# cherrymx1.net
KiCad netlist of a schematic drawn in EAGLE
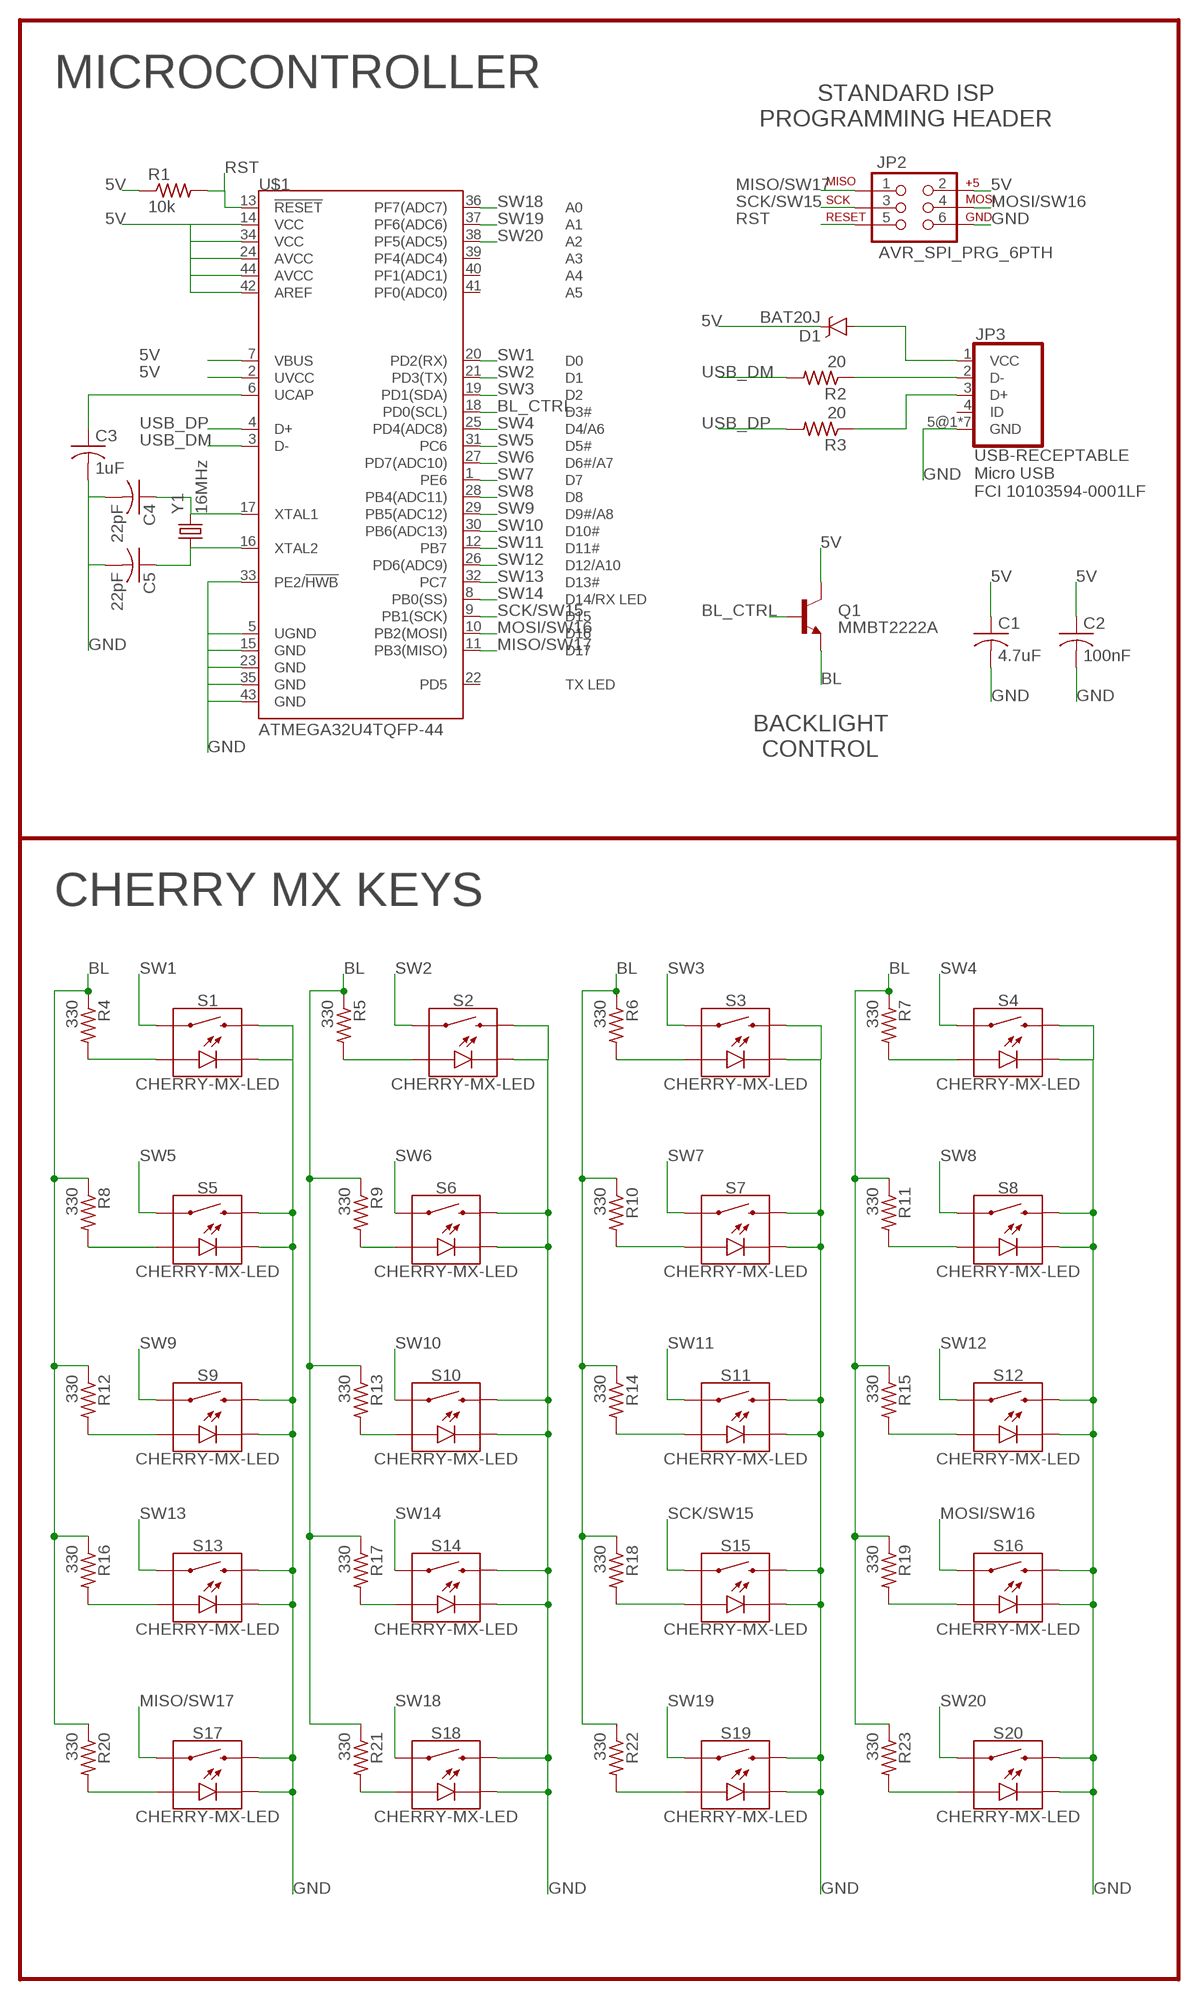
[diagram p0: schematic, sheet 1]

(export (version "E")
  (design (tool "Eeschema 10.0.6"))
  (components
    (comp (ref "C1")
      (value "4.7uF")
      (footprint "eagle-import:C0603")
      (libsource (lib "eagle-import") (part "C-USC0603"))
    )
    (comp (ref "C2")
      (value "100nF")
      (footprint "eagle-import:C0603")
      (libsource (lib "eagle-import") (part "C-USC0603"))
    )
    (comp (ref "C3")
      (value "1uF")
      (footprint "eagle-import:C0603")
      (libsource (lib "eagle-import") (part "C-USC0603"))
    )
    (comp (ref "C4")
      (value "22pF")
      (footprint "eagle-import:C0603")
      (libsource (lib "eagle-import") (part "C-USC0603"))
    )
    (comp (ref "C5")
      (value "22pF")
      (footprint "eagle-import:C0603")
      (libsource (lib "eagle-import") (part "C-USC0603"))
    )
    (comp (ref "D1")
      (value "BAT20J")
      (footprint "eagle-import:SOD-323")
      (libsource (lib "eagle-import") (part "DIODE-SCHOTTKY-BAT20J"))
    )
    (comp (ref "JP2")
      (value "AVR_SPI_PRG_6PTH")
      (footprint "eagle-import:2X3")
      (libsource (lib "eagle-import") (part "AVR_SPI_PRG_6PTH"))
    )
    (comp (ref "JP3")
      (value "USB-RECEPTABLE")
      (footprint "eagle-import:FCI-10103594-0001LF")
      (libsource (lib "eagle-import") (part "USB-RECEPTABLE"))
    )
    (comp (ref "Q1")
      (value "MMBT2222A")
      (footprint "eagle-import:SOT23-3")
      (libsource (lib "eagle-import") (part "TRANSISTOR_NPNMMBT2222A"))
    )
    (comp (ref "R1")
      (value "10k")
      (footprint "eagle-import:R0603")
      (libsource (lib "eagle-import") (part "R-US_R0603"))
    )
    (comp (ref "R2")
      (value "20")
      (footprint "eagle-import:R0603")
      (libsource (lib "eagle-import") (part "R-US_R0603"))
    )
    (comp (ref "R3")
      (value "20")
      (footprint "eagle-import:R0603")
      (libsource (lib "eagle-import") (part "R-US_R0603"))
    )
    (comp (ref "R4")
      (value "330")
      (footprint "eagle-import:R0603")
      (libsource (lib "eagle-import") (part "R-US_R0603"))
    )
    (comp (ref "R5")
      (value "330")
      (footprint "eagle-import:R0603")
      (libsource (lib "eagle-import") (part "R-US_R0603"))
    )
    (comp (ref "R6")
      (value "330")
      (footprint "eagle-import:R0603")
      (libsource (lib "eagle-import") (part "R-US_R0603"))
    )
    (comp (ref "R7")
      (value "330")
      (footprint "eagle-import:R0603")
      (libsource (lib "eagle-import") (part "R-US_R0603"))
    )
    (comp (ref "R8")
      (value "330")
      (footprint "eagle-import:R0603")
      (libsource (lib "eagle-import") (part "R-US_R0603"))
    )
    (comp (ref "R9")
      (value "330")
      (footprint "eagle-import:R0603")
      (libsource (lib "eagle-import") (part "R-US_R0603"))
    )
    (comp (ref "R10")
      (value "330")
      (footprint "eagle-import:R0603")
      (libsource (lib "eagle-import") (part "R-US_R0603"))
    )
    (comp (ref "R11")
      (value "330")
      (footprint "eagle-import:R0603")
      (libsource (lib "eagle-import") (part "R-US_R0603"))
    )
    (comp (ref "R12")
      (value "330")
      (footprint "eagle-import:R0603")
      (libsource (lib "eagle-import") (part "R-US_R0603"))
    )
    (comp (ref "R13")
      (value "330")
      (footprint "eagle-import:R0603")
      (libsource (lib "eagle-import") (part "R-US_R0603"))
    )
    (comp (ref "R14")
      (value "330")
      (footprint "eagle-import:R0603")
      (libsource (lib "eagle-import") (part "R-US_R0603"))
    )
    (comp (ref "R15")
      (value "330")
      (footprint "eagle-import:R0603")
      (libsource (lib "eagle-import") (part "R-US_R0603"))
    )
    (comp (ref "R16")
      (value "330")
      (footprint "eagle-import:R0603")
      (libsource (lib "eagle-import") (part "R-US_R0603"))
    )
    (comp (ref "R17")
      (value "330")
      (footprint "eagle-import:R0603")
      (libsource (lib "eagle-import") (part "R-US_R0603"))
    )
    (comp (ref "R18")
      (value "330")
      (footprint "eagle-import:R0603")
      (libsource (lib "eagle-import") (part "R-US_R0603"))
    )
    (comp (ref "R19")
      (value "330")
      (footprint "eagle-import:R0603")
      (libsource (lib "eagle-import") (part "R-US_R0603"))
    )
    (comp (ref "R20")
      (value "330")
      (footprint "eagle-import:R0603")
      (libsource (lib "eagle-import") (part "R-US_R0603"))
    )
    (comp (ref "R21")
      (value "330")
      (footprint "eagle-import:R0603")
      (libsource (lib "eagle-import") (part "R-US_R0603"))
    )
    (comp (ref "R22")
      (value "330")
      (footprint "eagle-import:R0603")
      (libsource (lib "eagle-import") (part "R-US_R0603"))
    )
    (comp (ref "R23")
      (value "330")
      (footprint "eagle-import:R0603")
      (libsource (lib "eagle-import") (part "R-US_R0603"))
    )
    (comp (ref "S1")
      (value "CHERRY-MX-LED")
      (footprint "eagle-import:CHERRY-MX-LED")
      (libsource (lib "eagle-import") (part "CHERRY-MX-LED"))
    )
    (comp (ref "S2")
      (value "CHERRY-MX-LED")
      (footprint "eagle-import:CHERRY-MX-LED")
      (libsource (lib "eagle-import") (part "CHERRY-MX-LED"))
    )
    (comp (ref "S3")
      (value "CHERRY-MX-LED")
      (footprint "eagle-import:CHERRY-MX-LED")
      (libsource (lib "eagle-import") (part "CHERRY-MX-LED"))
    )
    (comp (ref "S4")
      (value "CHERRY-MX-LED")
      (footprint "eagle-import:CHERRY-MX-LED")
      (libsource (lib "eagle-import") (part "CHERRY-MX-LED"))
    )
    (comp (ref "S5")
      (value "CHERRY-MX-LED")
      (footprint "eagle-import:CHERRY-MX-LED")
      (libsource (lib "eagle-import") (part "CHERRY-MX-LED"))
    )
    (comp (ref "S6")
      (value "CHERRY-MX-LED")
      (footprint "eagle-import:CHERRY-MX-LED")
      (libsource (lib "eagle-import") (part "CHERRY-MX-LED"))
    )
    (comp (ref "S7")
      (value "CHERRY-MX-LED")
      (footprint "eagle-import:CHERRY-MX-LED")
      (libsource (lib "eagle-import") (part "CHERRY-MX-LED"))
    )
    (comp (ref "S8")
      (value "CHERRY-MX-LED")
      (footprint "eagle-import:CHERRY-MX-LED")
      (libsource (lib "eagle-import") (part "CHERRY-MX-LED"))
    )
    (comp (ref "S9")
      (value "CHERRY-MX-LED")
      (footprint "eagle-import:CHERRY-MX-LED")
      (libsource (lib "eagle-import") (part "CHERRY-MX-LED"))
    )
    (comp (ref "S10")
      (value "CHERRY-MX-LED")
      (footprint "eagle-import:CHERRY-MX-LED")
      (libsource (lib "eagle-import") (part "CHERRY-MX-LED"))
    )
    (comp (ref "S11")
      (value "CHERRY-MX-LED")
      (footprint "eagle-import:CHERRY-MX-LED")
      (libsource (lib "eagle-import") (part "CHERRY-MX-LED"))
    )
    (comp (ref "S12")
      (value "CHERRY-MX-LED")
      (footprint "eagle-import:CHERRY-MX-LED")
      (libsource (lib "eagle-import") (part "CHERRY-MX-LED"))
    )
    (comp (ref "S13")
      (value "CHERRY-MX-LED")
      (footprint "eagle-import:CHERRY-MX-LED")
      (libsource (lib "eagle-import") (part "CHERRY-MX-LED"))
    )
    (comp (ref "S14")
      (value "CHERRY-MX-LED")
      (footprint "eagle-import:CHERRY-MX-LED")
      (libsource (lib "eagle-import") (part "CHERRY-MX-LED"))
    )
    (comp (ref "S15")
      (value "CHERRY-MX-LED")
      (footprint "eagle-import:CHERRY-MX-LED")
      (libsource (lib "eagle-import") (part "CHERRY-MX-LED"))
    )
    (comp (ref "S16")
      (value "CHERRY-MX-LED")
      (footprint "eagle-import:CHERRY-MX-LED")
      (libsource (lib "eagle-import") (part "CHERRY-MX-LED"))
    )
    (comp (ref "S17")
      (value "CHERRY-MX-LED")
      (footprint "eagle-import:CHERRY-MX-LED")
      (libsource (lib "eagle-import") (part "CHERRY-MX-LED"))
    )
    (comp (ref "S18")
      (value "CHERRY-MX-LED")
      (footprint "eagle-import:CHERRY-MX-LED")
      (libsource (lib "eagle-import") (part "CHERRY-MX-LED"))
    )
    (comp (ref "S19")
      (value "CHERRY-MX-LED")
      (footprint "eagle-import:CHERRY-MX-LED")
      (libsource (lib "eagle-import") (part "CHERRY-MX-LED"))
    )
    (comp (ref "S20")
      (value "CHERRY-MX-LED")
      (footprint "eagle-import:CHERRY-MX-LED")
      (libsource (lib "eagle-import") (part "CHERRY-MX-LED"))
    )
    (comp (ref "U$1")
      (value "ATMEGA32U4TQFP-44")
      (footprint "eagle-import:TQFP44")
      (libsource (lib "eagle-import") (part "ATMEGA32U4TQFP-44"))
    )
    (comp (ref "Y1")
      (value "16MHz")
      (footprint "eagle-import:CRYSTAL-SMD-5X3")
      (libsource (lib "eagle-import") (part "CRYSTAL5X3"))
    )
  )
  (nets
    (net (code "1") (name "/5V") (class "Default")
      (node (ref "C1") (pin "1") (pinfunction "1_1") (pintype "passive"))
      (node (ref "C2") (pin "1") (pinfunction "1_1") (pintype "passive"))
      (node (ref "D1") (pin "C") (pinfunction "C_C") (pintype "passive"))
      (node (ref "JP2") (pin "2") (pinfunction "2_2") (pintype "passive"))
      (node (ref "Q1") (pin "3") (pinfunction "C_3") (pintype "passive"))
      (node (ref "R1") (pin "1") (pinfunction "1_1") (pintype "passive"))
      (node (ref "U$1") (pin "14") (pinfunction "VCC_14") (pintype "bidirectional"))
      (node (ref "U$1") (pin "2") (pinfunction "UVCC_2") (pintype "bidirectional"))
      (node (ref "U$1") (pin "24") (pinfunction "AVCC_24") (pintype "bidirectional"))
      (node (ref "U$1") (pin "34") (pinfunction "VCC_34") (pintype "bidirectional"))
      (node (ref "U$1") (pin "42") (pinfunction "AREF_42") (pintype "bidirectional"))
      (node (ref "U$1") (pin "44") (pinfunction "AVCC_44") (pintype "bidirectional"))
      (node (ref "U$1") (pin "7") (pinfunction "VBUS_7") (pintype "bidirectional"))
    )
    (net (code "2") (name "/BL") (class "Default")
      (node (ref "Q1") (pin "2") (pinfunction "E_2") (pintype "passive"))
      (node (ref "R10") (pin "1") (pinfunction "1_1") (pintype "passive"))
      (node (ref "R11") (pin "1") (pinfunction "1_1") (pintype "passive"))
      (node (ref "R12") (pin "1") (pinfunction "1_1") (pintype "passive"))
      (node (ref "R13") (pin "1") (pinfunction "1_1") (pintype "passive"))
      (node (ref "R14") (pin "1") (pinfunction "1_1") (pintype "passive"))
      (node (ref "R15") (pin "1") (pinfunction "1_1") (pintype "passive"))
      (node (ref "R16") (pin "1") (pinfunction "1_1") (pintype "passive"))
      (node (ref "R17") (pin "1") (pinfunction "1_1") (pintype "passive"))
      (node (ref "R18") (pin "1") (pinfunction "1_1") (pintype "passive"))
      (node (ref "R19") (pin "1") (pinfunction "1_1") (pintype "passive"))
      (node (ref "R20") (pin "1") (pinfunction "1_1") (pintype "passive"))
      (node (ref "R21") (pin "1") (pinfunction "1_1") (pintype "passive"))
      (node (ref "R22") (pin "1") (pinfunction "1_1") (pintype "passive"))
      (node (ref "R23") (pin "1") (pinfunction "1_1") (pintype "passive"))
      (node (ref "R4") (pin "1") (pinfunction "1_1") (pintype "passive"))
      (node (ref "R5") (pin "1") (pinfunction "1_1") (pintype "passive"))
      (node (ref "R6") (pin "1") (pinfunction "1_1") (pintype "passive"))
      (node (ref "R7") (pin "1") (pinfunction "1_1") (pintype "passive"))
      (node (ref "R8") (pin "1") (pinfunction "1_1") (pintype "passive"))
      (node (ref "R9") (pin "1") (pinfunction "1_1") (pintype "passive"))
    )
    (net (code "3") (name "/BL_CTRL") (class "Default")
      (node (ref "Q1") (pin "1") (pinfunction "B_1") (pintype "passive"))
      (node (ref "U$1") (pin "18") (pinfunction "PD0(SCL)_18") (pintype "bidirectional"))
    )
    (net (code "4") (name "/GND") (class "Default")
      (node (ref "C1") (pin "2") (pinfunction "2_2") (pintype "passive"))
      (node (ref "C2") (pin "2") (pinfunction "2_2") (pintype "passive"))
      (node (ref "C3") (pin "2") (pinfunction "2_2") (pintype "passive"))
      (node (ref "C4") (pin "2") (pinfunction "2_2") (pintype "passive"))
      (node (ref "C5") (pin "2") (pinfunction "2_2") (pintype "passive"))
      (node (ref "JP2") (pin "6") (pinfunction "6_6") (pintype "passive"))
      (node (ref "JP3") (pin "5@1") (pinfunction "GND_5@1") (pintype "bidirectional"))
      (node (ref "JP3") (pin "5@2") (pinfunction "GND_5@2") (pintype "bidirectional"))
      (node (ref "JP3") (pin "5@3") (pinfunction "GND_5@3") (pintype "bidirectional"))
      (node (ref "JP3") (pin "5@4") (pinfunction "GND_5@4") (pintype "bidirectional"))
      (node (ref "JP3") (pin "5@5") (pinfunction "GND_5@5") (pintype "bidirectional"))
      (node (ref "JP3") (pin "5@6") (pinfunction "GND_5@6") (pintype "bidirectional"))
      (node (ref "JP3") (pin "5@7") (pinfunction "GND_5@7") (pintype "bidirectional"))
      (node (ref "S1") (pin "K") (pinfunction "C_K") (pintype "passive"))
      (node (ref "S1") (pin "S2") (pinfunction "S2_S2") (pintype "passive"))
      (node (ref "S10") (pin "K") (pinfunction "C_K") (pintype "passive"))
      (node (ref "S10") (pin "S2") (pinfunction "S2_S2") (pintype "passive"))
      (node (ref "S11") (pin "K") (pinfunction "C_K") (pintype "passive"))
      (node (ref "S11") (pin "S2") (pinfunction "S2_S2") (pintype "passive"))
      (node (ref "S12") (pin "K") (pinfunction "C_K") (pintype "passive"))
      (node (ref "S12") (pin "S2") (pinfunction "S2_S2") (pintype "passive"))
      (node (ref "S13") (pin "K") (pinfunction "C_K") (pintype "passive"))
      (node (ref "S13") (pin "S2") (pinfunction "S2_S2") (pintype "passive"))
      (node (ref "S14") (pin "K") (pinfunction "C_K") (pintype "passive"))
      (node (ref "S14") (pin "S2") (pinfunction "S2_S2") (pintype "passive"))
      (node (ref "S15") (pin "K") (pinfunction "C_K") (pintype "passive"))
      (node (ref "S15") (pin "S2") (pinfunction "S2_S2") (pintype "passive"))
      (node (ref "S16") (pin "K") (pinfunction "C_K") (pintype "passive"))
      (node (ref "S16") (pin "S2") (pinfunction "S2_S2") (pintype "passive"))
      (node (ref "S17") (pin "K") (pinfunction "C_K") (pintype "passive"))
      (node (ref "S17") (pin "S2") (pinfunction "S2_S2") (pintype "passive"))
      (node (ref "S18") (pin "K") (pinfunction "C_K") (pintype "passive"))
      (node (ref "S18") (pin "S2") (pinfunction "S2_S2") (pintype "passive"))
      (node (ref "S19") (pin "K") (pinfunction "C_K") (pintype "passive"))
      (node (ref "S19") (pin "S2") (pinfunction "S2_S2") (pintype "passive"))
      (node (ref "S2") (pin "K") (pinfunction "C_K") (pintype "passive"))
      (node (ref "S2") (pin "S2") (pinfunction "S2_S2") (pintype "passive"))
      (node (ref "S20") (pin "K") (pinfunction "C_K") (pintype "passive"))
      (node (ref "S20") (pin "S2") (pinfunction "S2_S2") (pintype "passive"))
      (node (ref "S3") (pin "K") (pinfunction "C_K") (pintype "passive"))
      (node (ref "S3") (pin "S2") (pinfunction "S2_S2") (pintype "passive"))
      (node (ref "S4") (pin "K") (pinfunction "C_K") (pintype "passive"))
      (node (ref "S4") (pin "S2") (pinfunction "S2_S2") (pintype "passive"))
      (node (ref "S5") (pin "K") (pinfunction "C_K") (pintype "passive"))
      (node (ref "S5") (pin "S2") (pinfunction "S2_S2") (pintype "passive"))
      (node (ref "S6") (pin "K") (pinfunction "C_K") (pintype "passive"))
      (node (ref "S6") (pin "S2") (pinfunction "S2_S2") (pintype "passive"))
      (node (ref "S7") (pin "K") (pinfunction "C_K") (pintype "passive"))
      (node (ref "S7") (pin "S2") (pinfunction "S2_S2") (pintype "passive"))
      (node (ref "S8") (pin "K") (pinfunction "C_K") (pintype "passive"))
      (node (ref "S8") (pin "S2") (pinfunction "S2_S2") (pintype "passive"))
      (node (ref "S9") (pin "K") (pinfunction "C_K") (pintype "passive"))
      (node (ref "S9") (pin "S2") (pinfunction "S2_S2") (pintype "passive"))
      (node (ref "U$1") (pin "15") (pinfunction "GND_15") (pintype "bidirectional"))
      (node (ref "U$1") (pin "23") (pinfunction "GND_23") (pintype "bidirectional"))
      (node (ref "U$1") (pin "33") (pinfunction "PE2/~{HWB}_33") (pintype "bidirectional"))
      (node (ref "U$1") (pin "35") (pinfunction "GND_35") (pintype "bidirectional"))
      (node (ref "U$1") (pin "43") (pinfunction "GND_43") (pintype "bidirectional"))
      (node (ref "U$1") (pin "5") (pinfunction "UGND_5") (pintype "bidirectional"))
    )
    (net (code "5") (name "/MISO{slash}SW17") (class "Default")
      (node (ref "JP2") (pin "1") (pinfunction "1_1") (pintype "passive"))
      (node (ref "S17") (pin "S1") (pinfunction "S1_S1") (pintype "passive"))
      (node (ref "U$1") (pin "11") (pinfunction "PB3(MISO)_11") (pintype "bidirectional"))
    )
    (net (code "6") (name "/MOSI{slash}SW16") (class "Default")
      (node (ref "JP2") (pin "4") (pinfunction "4_4") (pintype "passive"))
      (node (ref "S16") (pin "S1") (pinfunction "S1_S1") (pintype "passive"))
      (node (ref "U$1") (pin "10") (pinfunction "PB2(MOSI)_10") (pintype "bidirectional"))
    )
    (net (code "7") (name "/RST") (class "Default")
      (node (ref "JP2") (pin "5") (pinfunction "5_5") (pintype "passive"))
      (node (ref "R1") (pin "2") (pinfunction "2_2") (pintype "passive"))
      (node (ref "U$1") (pin "13") (pinfunction "~{RESET}_13") (pintype "bidirectional"))
    )
    (net (code "8") (name "/SCK{slash}SW15") (class "Default")
      (node (ref "JP2") (pin "3") (pinfunction "3_3") (pintype "passive"))
      (node (ref "S15") (pin "S1") (pinfunction "S1_S1") (pintype "passive"))
      (node (ref "U$1") (pin "9") (pinfunction "PB1(SCK)_9") (pintype "bidirectional"))
    )
    (net (code "9") (name "/SW1") (class "Default")
      (node (ref "S1") (pin "S1") (pinfunction "S1_S1") (pintype "passive"))
      (node (ref "U$1") (pin "20") (pinfunction "PD2(RX)_20") (pintype "bidirectional"))
    )
    (net (code "10") (name "/SW2") (class "Default")
      (node (ref "S2") (pin "S1") (pinfunction "S1_S1") (pintype "passive"))
      (node (ref "U$1") (pin "21") (pinfunction "PD3(TX)_21") (pintype "bidirectional"))
    )
    (net (code "11") (name "/SW3") (class "Default")
      (node (ref "S3") (pin "S1") (pinfunction "S1_S1") (pintype "passive"))
      (node (ref "U$1") (pin "19") (pinfunction "PD1(SDA)_19") (pintype "bidirectional"))
    )
    (net (code "12") (name "/SW4") (class "Default")
      (node (ref "S4") (pin "S1") (pinfunction "S1_S1") (pintype "passive"))
      (node (ref "U$1") (pin "25") (pinfunction "PD4(ADC8)_25") (pintype "bidirectional"))
    )
    (net (code "13") (name "/SW5") (class "Default")
      (node (ref "S5") (pin "S1") (pinfunction "S1_S1") (pintype "passive"))
      (node (ref "U$1") (pin "31") (pinfunction "PC6_31") (pintype "bidirectional"))
    )
    (net (code "14") (name "/SW6") (class "Default")
      (node (ref "S6") (pin "S1") (pinfunction "S1_S1") (pintype "passive"))
      (node (ref "U$1") (pin "27") (pinfunction "PD7(ADC10)_27") (pintype "bidirectional"))
    )
    (net (code "15") (name "/SW7") (class "Default")
      (node (ref "S7") (pin "S1") (pinfunction "S1_S1") (pintype "passive"))
      (node (ref "U$1") (pin "1") (pinfunction "PE6_1") (pintype "bidirectional"))
    )
    (net (code "16") (name "/SW8") (class "Default")
      (node (ref "S8") (pin "S1") (pinfunction "S1_S1") (pintype "passive"))
      (node (ref "U$1") (pin "28") (pinfunction "PB4(ADC11)_28") (pintype "bidirectional"))
    )
    (net (code "17") (name "/SW9") (class "Default")
      (node (ref "S9") (pin "S1") (pinfunction "S1_S1") (pintype "passive"))
      (node (ref "U$1") (pin "29") (pinfunction "PB5(ADC12)_29") (pintype "bidirectional"))
    )
    (net (code "18") (name "/SW10") (class "Default")
      (node (ref "S10") (pin "S1") (pinfunction "S1_S1") (pintype "passive"))
      (node (ref "U$1") (pin "30") (pinfunction "PB6(ADC13)_30") (pintype "bidirectional"))
    )
    (net (code "19") (name "/SW11") (class "Default")
      (node (ref "S11") (pin "S1") (pinfunction "S1_S1") (pintype "passive"))
      (node (ref "U$1") (pin "12") (pinfunction "PB7_12") (pintype "bidirectional"))
    )
    (net (code "20") (name "/SW12") (class "Default")
      (node (ref "S12") (pin "S1") (pinfunction "S1_S1") (pintype "passive"))
      (node (ref "U$1") (pin "26") (pinfunction "PD6(ADC9)_26") (pintype "bidirectional"))
    )
    (net (code "21") (name "/SW13") (class "Default")
      (node (ref "S13") (pin "S1") (pinfunction "S1_S1") (pintype "passive"))
      (node (ref "U$1") (pin "32") (pinfunction "PC7_32") (pintype "bidirectional"))
    )
    (net (code "22") (name "/SW14") (class "Default")
      (node (ref "S14") (pin "S1") (pinfunction "S1_S1") (pintype "passive"))
      (node (ref "U$1") (pin "8") (pinfunction "PB0(SS)_8") (pintype "bidirectional"))
    )
    (net (code "23") (name "/SW18") (class "Default")
      (node (ref "S18") (pin "S1") (pinfunction "S1_S1") (pintype "passive"))
      (node (ref "U$1") (pin "36") (pinfunction "PF7(ADC7)_36") (pintype "bidirectional"))
    )
    (net (code "24") (name "/SW19") (class "Default")
      (node (ref "S19") (pin "S1") (pinfunction "S1_S1") (pintype "passive"))
      (node (ref "U$1") (pin "37") (pinfunction "PF6(ADC6)_37") (pintype "bidirectional"))
    )
    (net (code "25") (name "/SW20") (class "Default")
      (node (ref "S20") (pin "S1") (pinfunction "S1_S1") (pintype "passive"))
      (node (ref "U$1") (pin "38") (pinfunction "PF5(ADC5)_38") (pintype "bidirectional"))
    )
    (net (code "26") (name "/USB_DM") (class "Default")
      (node (ref "R2") (pin "2") (pinfunction "2_2") (pintype "passive"))
      (node (ref "U$1") (pin "3") (pinfunction "D-_3") (pintype "bidirectional"))
    )
    (net (code "27") (name "/USB_DP") (class "Default")
      (node (ref "R3") (pin "2") (pinfunction "2_2") (pintype "passive"))
      (node (ref "U$1") (pin "4") (pinfunction "D+_4") (pintype "bidirectional"))
    )
    (net (code "28") (name "Net-(JP3-D+)") (class "Default")
      (node (ref "JP3") (pin "3") (pinfunction "D+_3") (pintype "bidirectional"))
      (node (ref "R3") (pin "1") (pinfunction "1_1") (pintype "passive"))
    )
    (net (code "29") (name "Net-(JP3-D-)") (class "Default")
      (node (ref "JP3") (pin "2") (pinfunction "D-_2") (pintype "bidirectional"))
      (node (ref "R2") (pin "1") (pinfunction "1_1") (pintype "passive"))
    )
    (net (code "30") (name "Net-(JP3-VCC)") (class "Default")
      (node (ref "D1") (pin "A") (pinfunction "A_A") (pintype "passive"))
      (node (ref "JP3") (pin "1") (pinfunction "VCC_1") (pintype "bidirectional"))
    )
    (net (code "31") (name "Net-(R4-Pad2)") (class "Default")
      (node (ref "R4") (pin "2") (pinfunction "2_2") (pintype "passive"))
      (node (ref "S1") (pin "A") (pinfunction "A_A") (pintype "passive"))
    )
    (net (code "32") (name "Net-(R5-Pad2)") (class "Default")
      (node (ref "R5") (pin "2") (pinfunction "2_2") (pintype "passive"))
      (node (ref "S2") (pin "A") (pinfunction "A_A") (pintype "passive"))
    )
    (net (code "33") (name "Net-(R6-Pad2)") (class "Default")
      (node (ref "R6") (pin "2") (pinfunction "2_2") (pintype "passive"))
      (node (ref "S3") (pin "A") (pinfunction "A_A") (pintype "passive"))
    )
    (net (code "34") (name "Net-(R7-Pad2)") (class "Default")
      (node (ref "R7") (pin "2") (pinfunction "2_2") (pintype "passive"))
      (node (ref "S4") (pin "A") (pinfunction "A_A") (pintype "passive"))
    )
    (net (code "35") (name "Net-(R8-Pad2)") (class "Default")
      (node (ref "R8") (pin "2") (pinfunction "2_2") (pintype "passive"))
      (node (ref "S5") (pin "A") (pinfunction "A_A") (pintype "passive"))
    )
    (net (code "36") (name "Net-(R9-Pad2)") (class "Default")
      (node (ref "R9") (pin "2") (pinfunction "2_2") (pintype "passive"))
      (node (ref "S6") (pin "A") (pinfunction "A_A") (pintype "passive"))
    )
    (net (code "37") (name "Net-(R10-Pad2)") (class "Default")
      (node (ref "R10") (pin "2") (pinfunction "2_2") (pintype "passive"))
      (node (ref "S7") (pin "A") (pinfunction "A_A") (pintype "passive"))
    )
    (net (code "38") (name "Net-(R11-Pad2)") (class "Default")
      (node (ref "R11") (pin "2") (pinfunction "2_2") (pintype "passive"))
      (node (ref "S8") (pin "A") (pinfunction "A_A") (pintype "passive"))
    )
    (net (code "39") (name "Net-(R12-Pad2)") (class "Default")
      (node (ref "R12") (pin "2") (pinfunction "2_2") (pintype "passive"))
      (node (ref "S9") (pin "A") (pinfunction "A_A") (pintype "passive"))
    )
    (net (code "40") (name "Net-(R13-Pad2)") (class "Default")
      (node (ref "R13") (pin "2") (pinfunction "2_2") (pintype "passive"))
      (node (ref "S10") (pin "A") (pinfunction "A_A") (pintype "passive"))
    )
    (net (code "41") (name "Net-(R14-Pad2)") (class "Default")
      (node (ref "R14") (pin "2") (pinfunction "2_2") (pintype "passive"))
      (node (ref "S11") (pin "A") (pinfunction "A_A") (pintype "passive"))
    )
    (net (code "42") (name "Net-(R15-Pad2)") (class "Default")
      (node (ref "R15") (pin "2") (pinfunction "2_2") (pintype "passive"))
      (node (ref "S12") (pin "A") (pinfunction "A_A") (pintype "passive"))
    )
    (net (code "43") (name "Net-(R16-Pad2)") (class "Default")
      (node (ref "R16") (pin "2") (pinfunction "2_2") (pintype "passive"))
      (node (ref "S13") (pin "A") (pinfunction "A_A") (pintype "passive"))
    )
    (net (code "44") (name "Net-(R17-Pad2)") (class "Default")
      (node (ref "R17") (pin "2") (pinfunction "2_2") (pintype "passive"))
      (node (ref "S14") (pin "A") (pinfunction "A_A") (pintype "passive"))
    )
    (net (code "45") (name "Net-(R18-Pad2)") (class "Default")
      (node (ref "R18") (pin "2") (pinfunction "2_2") (pintype "passive"))
      (node (ref "S15") (pin "A") (pinfunction "A_A") (pintype "passive"))
    )
    (net (code "46") (name "Net-(R19-Pad2)") (class "Default")
      (node (ref "R19") (pin "2") (pinfunction "2_2") (pintype "passive"))
      (node (ref "S16") (pin "A") (pinfunction "A_A") (pintype "passive"))
    )
    (net (code "47") (name "Net-(R20-Pad2)") (class "Default")
      (node (ref "R20") (pin "2") (pinfunction "2_2") (pintype "passive"))
      (node (ref "S17") (pin "A") (pinfunction "A_A") (pintype "passive"))
    )
    (net (code "48") (name "Net-(R21-Pad2)") (class "Default")
      (node (ref "R21") (pin "2") (pinfunction "2_2") (pintype "passive"))
      (node (ref "S18") (pin "A") (pinfunction "A_A") (pintype "passive"))
    )
    (net (code "49") (name "Net-(R22-Pad2)") (class "Default")
      (node (ref "R22") (pin "2") (pinfunction "2_2") (pintype "passive"))
      (node (ref "S19") (pin "A") (pinfunction "A_A") (pintype "passive"))
    )
    (net (code "50") (name "Net-(R23-Pad2)") (class "Default")
      (node (ref "R23") (pin "2") (pinfunction "2_2") (pintype "passive"))
      (node (ref "S20") (pin "A") (pinfunction "A_A") (pintype "passive"))
    )
    (net (code "51") (name "Net-(U$1-UCAP)") (class "Default")
      (node (ref "C3") (pin "1") (pinfunction "1_1") (pintype "passive"))
      (node (ref "U$1") (pin "6") (pinfunction "UCAP_6") (pintype "bidirectional"))
    )
    (net (code "52") (name "Net-(U$1-XTAL1)") (class "Default")
      (node (ref "C4") (pin "1") (pinfunction "1_1") (pintype "passive"))
      (node (ref "U$1") (pin "17") (pinfunction "XTAL1_17") (pintype "bidirectional"))
      (node (ref "Y1") (pin "3") (pinfunction "2_3") (pintype "passive"))
    )
    (net (code "53") (name "Net-(U$1-XTAL2)") (class "Default")
      (node (ref "C5") (pin "1") (pinfunction "1_1") (pintype "passive"))
      (node (ref "U$1") (pin "16") (pinfunction "XTAL2_16") (pintype "bidirectional"))
      (node (ref "Y1") (pin "1") (pinfunction "1_1") (pintype "passive"))
    )
    (net (code "54") (name "unconnected-(JP3-ID-Pad4)") (class "Default")
      (node (ref "JP3") (pin "4") (pinfunction "ID_4") (pintype "bidirectional"))
    )
    (net (code "55") (name "unconnected-(U$1-PD5-Pad22)") (class "Default")
      (node (ref "U$1") (pin "22") (pinfunction "PD5_22") (pintype "bidirectional"))
    )
    (net (code "56") (name "unconnected-(U$1-PF0(ADC0)-Pad41)") (class "Default")
      (node (ref "U$1") (pin "41") (pinfunction "PF0(ADC0)_41") (pintype "bidirectional"))
    )
    (net (code "57") (name "unconnected-(U$1-PF1(ADC1)-Pad40)") (class "Default")
      (node (ref "U$1") (pin "40") (pinfunction "PF1(ADC1)_40") (pintype "bidirectional"))
    )
    (net (code "58") (name "unconnected-(U$1-PF4(ADC4)-Pad39)") (class "Default")
      (node (ref "U$1") (pin "39") (pinfunction "PF4(ADC4)_39") (pintype "bidirectional"))
    )
  )
)
